# Artemis_Charger_Mod_PCB.net
KiCad netlist of a schematic drawn in EAGLE
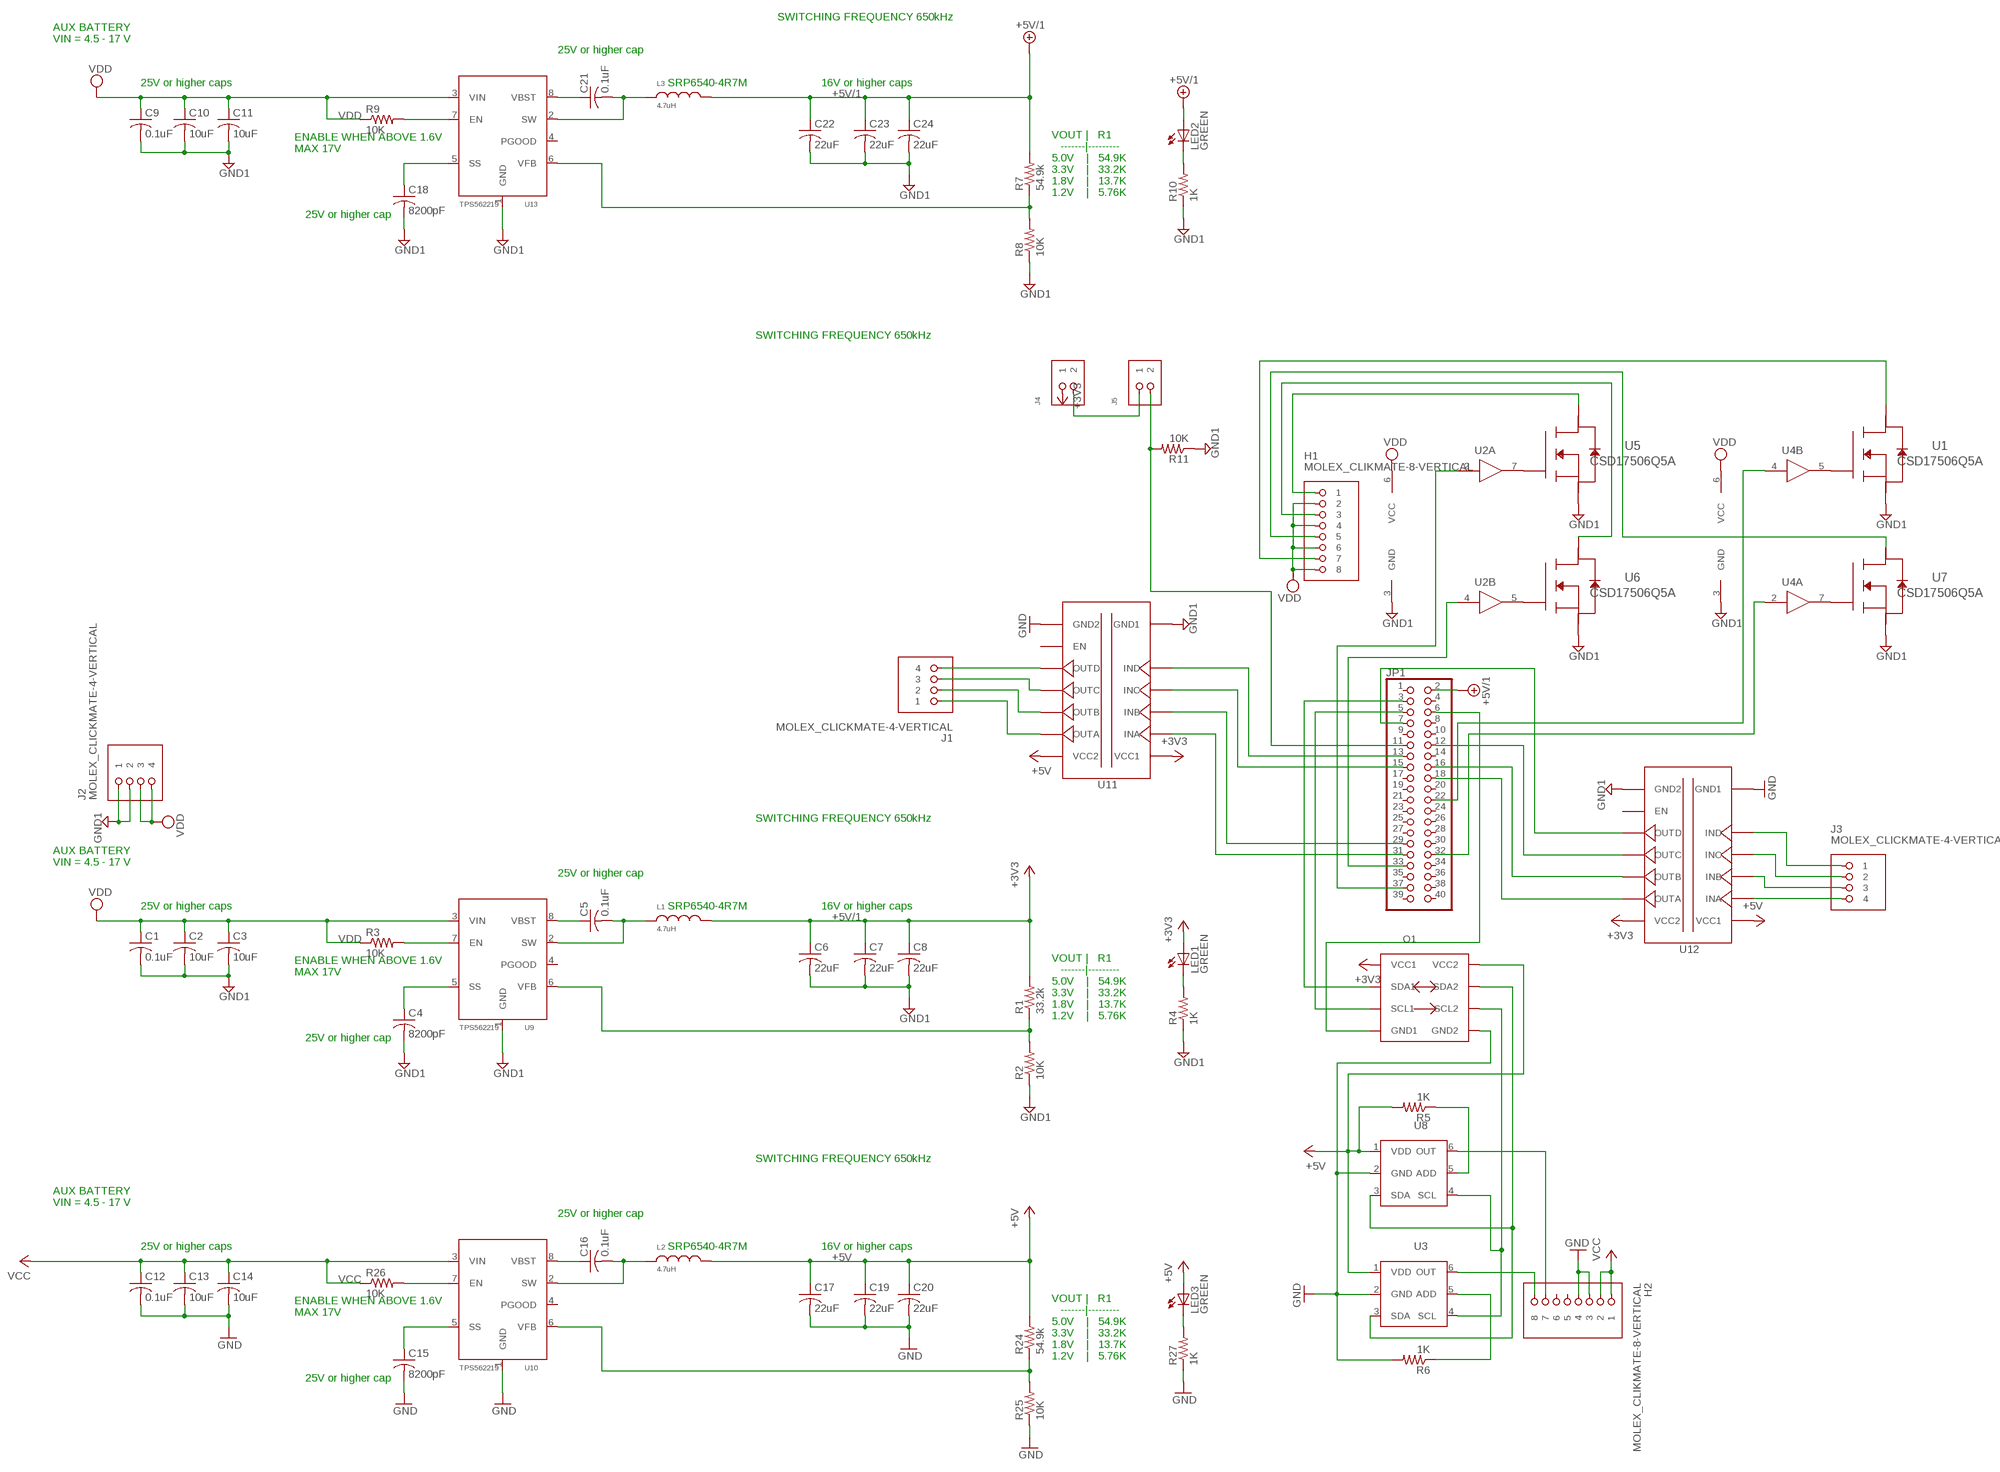
[diagram p0: schematic, sheet 1]

(export (version "E")
  (design (tool "Eeschema 10.0.6"))
  (components
    (comp (ref "C1")
      (value "0.1uF")
      (footprint "eagle-import:C0805")
      (fields (field (name "PARTNO") "GRM21BR71E104KA01L"))
      (libsource (lib "eagle-import") (part "C-USC0805"))
    )
    (comp (ref "C2")
      (value "10uF")
      (footprint "eagle-import:C0805")
      (fields (field (name "PARTNO") "GRM21BR61E106KA73L"))
      (libsource (lib "eagle-import") (part "C-USC0805"))
    )
    (comp (ref "C3")
      (value "10uF")
      (footprint "eagle-import:C0805")
      (fields (field (name "PARTNO") "GRM21BR61E106KA73L"))
      (libsource (lib "eagle-import") (part "C-USC0805"))
    )
    (comp (ref "C4")
      (value "8200pF")
      (footprint "eagle-import:C0805")
      (fields (field (name "PARTNO") "C0805C822K5RACTU"))
      (libsource (lib "eagle-import") (part "C-USC0805"))
    )
    (comp (ref "C5")
      (value "0.1uF")
      (footprint "eagle-import:C0805")
      (fields (field (name "PARTNO") "GRM21BR71E104KA01L"))
      (libsource (lib "eagle-import") (part "C-USC0805"))
    )
    (comp (ref "C6")
      (value "22uF")
      (footprint "eagle-import:C0805")
      (fields (field (name "PARTNO") "C2012JB1E226M125AC"))
      (libsource (lib "eagle-import") (part "C-USC0805"))
    )
    (comp (ref "C7")
      (value "22uF")
      (footprint "eagle-import:C0805")
      (fields (field (name "PARTNO") "C2012JB1E226M125AC"))
      (libsource (lib "eagle-import") (part "C-USC0805"))
    )
    (comp (ref "C8")
      (value "22uF")
      (footprint "eagle-import:C0805")
      (fields (field (name "PARTNO") "C2012JB1E226M125AC"))
      (libsource (lib "eagle-import") (part "C-USC0805"))
    )
    (comp (ref "C9")
      (value "0.1uF")
      (footprint "eagle-import:C0805")
      (fields (field (name "PARTNO") "GRM21BR71E104KA01L"))
      (libsource (lib "eagle-import") (part "C-USC0805"))
    )
    (comp (ref "C10")
      (value "10uF")
      (footprint "eagle-import:C0805")
      (fields (field (name "PARTNO") "GRM21BR61E106KA73L"))
      (libsource (lib "eagle-import") (part "C-USC0805"))
    )
    (comp (ref "C11")
      (value "10uF")
      (footprint "eagle-import:C0805")
      (fields (field (name "PARTNO") "GRM21BR61E106KA73L"))
      (libsource (lib "eagle-import") (part "C-USC0805"))
    )
    (comp (ref "C12")
      (value "0.1uF")
      (footprint "eagle-import:C0805")
      (fields (field (name "PARTNO") "GRM21BR71E104KA01L"))
      (libsource (lib "eagle-import") (part "C-USC0805"))
    )
    (comp (ref "C13")
      (value "10uF")
      (footprint "eagle-import:C0805")
      (fields (field (name "PARTNO") "GRM21BR61E106KA73L"))
      (libsource (lib "eagle-import") (part "C-USC0805"))
    )
    (comp (ref "C14")
      (value "10uF")
      (footprint "eagle-import:C0805")
      (fields (field (name "PARTNO") "GRM21BR61E106KA73L"))
      (libsource (lib "eagle-import") (part "C-USC0805"))
    )
    (comp (ref "C15")
      (value "8200pF")
      (footprint "eagle-import:C0805")
      (fields (field (name "PARTNO") "C0805C822K5RACTU"))
      (libsource (lib "eagle-import") (part "C-USC0805"))
    )
    (comp (ref "C16")
      (value "0.1uF")
      (footprint "eagle-import:C0805")
      (fields (field (name "PARTNO") "GRM21BR71E104KA01L"))
      (libsource (lib "eagle-import") (part "C-USC0805"))
    )
    (comp (ref "C17")
      (value "22uF")
      (footprint "eagle-import:C0805")
      (fields (field (name "PARTNO") "C2012JB1E226M125AC"))
      (libsource (lib "eagle-import") (part "C-USC0805"))
    )
    (comp (ref "C18")
      (value "8200pF")
      (footprint "eagle-import:C0805")
      (fields (field (name "PARTNO") "C0805C822K5RACTU"))
      (libsource (lib "eagle-import") (part "C-USC0805"))
    )
    (comp (ref "C19")
      (value "22uF")
      (footprint "eagle-import:C0805")
      (fields (field (name "PARTNO") "C2012JB1E226M125AC"))
      (libsource (lib "eagle-import") (part "C-USC0805"))
    )
    (comp (ref "C20")
      (value "22uF")
      (footprint "eagle-import:C0805")
      (fields (field (name "PARTNO") "C2012JB1E226M125AC"))
      (libsource (lib "eagle-import") (part "C-USC0805"))
    )
    (comp (ref "C21")
      (value "0.1uF")
      (footprint "eagle-import:C0805")
      (fields (field (name "PARTNO") "GRM21BR71E104KA01L"))
      (libsource (lib "eagle-import") (part "C-USC0805"))
    )
    (comp (ref "C22")
      (value "22uF")
      (footprint "eagle-import:C0805")
      (fields (field (name "PARTNO") "C2012JB1E226M125AC"))
      (libsource (lib "eagle-import") (part "C-USC0805"))
    )
    (comp (ref "C23")
      (value "22uF")
      (footprint "eagle-import:C0805")
      (fields (field (name "PARTNO") "C2012JB1E226M125AC"))
      (libsource (lib "eagle-import") (part "C-USC0805"))
    )
    (comp (ref "C24")
      (value "22uF")
      (footprint "eagle-import:C0805")
      (fields (field (name "PARTNO") "C2012JB1E226M125AC"))
      (libsource (lib "eagle-import") (part "C-USC0805"))
    )
    (comp (ref "H1")
      (value "MOLEX_CLIKMATE-8-VERTICAL")
      (footprint "eagle-import:MOLEX-CLIKMATE-8-VERTICAL-HEADER")
      (libsource (lib "eagle-import") (part "MOLEX_CLIKMATE-8-VERTICAL"))
    )
    (comp (ref "H2")
      (value "MOLEX_CLIKMATE-8-VERTICAL")
      (footprint "eagle-import:MOLEX-CLIKMATE-8-VERTICAL-HEADER")
      (libsource (lib "eagle-import") (part "MOLEX_CLIKMATE-8-VERTICAL"))
    )
    (comp (ref "J1")
      (value "MOLEX_CLICKMATE-4-VERTICAL")
      (footprint "eagle-import:MOLEX-CLIKMATE-4-VERTICAL-HEADER")
      (libsource (lib "eagle-import") (part "MOLEX_CLICKMATE-4-VERTICAL"))
    )
    (comp (ref "J2")
      (value "MOLEX_CLICKMATE-4-VERTICAL")
      (footprint "eagle-import:MOLEX-CLIKMATE-4-VERTICAL-HEADER")
      (libsource (lib "eagle-import") (part "MOLEX_CLICKMATE-4-VERTICAL"))
    )
    (comp (ref "J3")
      (value "MOLEX_CLICKMATE-4-VERTICAL")
      (footprint "eagle-import:MOLEX-CLIKMATE-4-VERTICAL-HEADER")
      (libsource (lib "eagle-import") (part "MOLEX_CLICKMATE-4-VERTICAL"))
    )
    (comp (ref "J4")
      (value "MOLEX_CLICKMATE-2-VERTICAL")
      (footprint "eagle-import:MOLEX-CLIKMATE-2-VERTICAL-HEADER")
      (libsource (lib "eagle-import") (part "MOLEX_CLICKMATE-2-VERTICAL"))
    )
    (comp (ref "J5")
      (value "MOLEX_CLICKMATE-2-VERTICAL")
      (footprint "eagle-import:MOLEX-CLIKMATE-2-VERTICAL-HEADER")
      (libsource (lib "eagle-import") (part "MOLEX_CLICKMATE-2-VERTICAL"))
    )
    (comp (ref "JP1")
      (value "PINHD-2X20")
      (footprint "eagle-import:2X20")
      (libsource (lib "eagle-import") (part "PINHD-2X20"))
    )
    (comp (ref "L1")
      (value "4.7uH")
      (footprint "eagle-import:SRP6540")
      (fields (field (name "PARTNO") "SRP6540-4R7M"))
      (libsource (lib "eagle-import") (part "SRP6540"))
    )
    (comp (ref "L2")
      (value "4.7uH")
      (footprint "eagle-import:SRP6540")
      (fields (field (name "PARTNO") "SRP6540-4R7M"))
      (libsource (lib "eagle-import") (part "SRP6540"))
    )
    (comp (ref "L3")
      (value "4.7uH")
      (footprint "eagle-import:SRP6540")
      (fields (field (name "PARTNO") "SRP6540-4R7M"))
      (libsource (lib "eagle-import") (part "SRP6540"))
    )
    (comp (ref "LED1")
      (value "GREEN")
      (footprint "eagle-import:CHIPLED_0805")
      (fields (field (name "PARTNO") "598-8170-107F"))
      (libsource (lib "eagle-import") (part "LEDCHIPLED_0805"))
    )
    (comp (ref "LED2")
      (value "GREEN")
      (footprint "eagle-import:CHIPLED_0805")
      (fields (field (name "PARTNO") "598-8170-107F"))
      (libsource (lib "eagle-import") (part "LEDCHIPLED_0805"))
    )
    (comp (ref "LED3")
      (value "GREEN")
      (footprint "eagle-import:CHIPLED_0805")
      (fields (field (name "PARTNO") "598-8170-107F"))
      (libsource (lib "eagle-import") (part "LEDCHIPLED_0805"))
    )
    (comp (ref "O1")
      (value "ISO1541")
      (footprint "eagle-import:ISO1541")
      (libsource (lib "eagle-import") (part "ISO1541"))
    )
    (comp (ref "R1")
      (value "33.2k")
      (footprint "eagle-import:R0805")
      (fields (field (name "PARTNO") "ERA-6AEB5492V"))
      (libsource (lib "eagle-import") (part "R-US_R0805"))
    )
    (comp (ref "R2")
      (value "10K")
      (footprint "eagle-import:R0805")
      (fields (field (name "PARTNO") "ERJ-6ENF1002V"))
      (libsource (lib "eagle-import") (part "R-US_R0805"))
    )
    (comp (ref "R3")
      (value "10K")
      (footprint "eagle-import:R0805")
      (fields (field (name "PARTNO") "ERJ-6ENF1002V"))
      (libsource (lib "eagle-import") (part "R-US_R0805"))
    )
    (comp (ref "R4")
      (value "1K")
      (footprint "eagle-import:R0805")
      (fields (field (name "PARTNO") "ERJ-6ENF1001V"))
      (libsource (lib "eagle-import") (part "R-US_R0805"))
    )
    (comp (ref "R5")
      (value "1K")
      (footprint "eagle-import:R0805")
      (fields (field (name "PARTNO") "ERJ-6ENF1001V"))
      (libsource (lib "eagle-import") (part "R-US_R0805"))
    )
    (comp (ref "R6")
      (value "1K")
      (footprint "eagle-import:R0805")
      (fields (field (name "PARTNO") "ERJ-6ENF1001V"))
      (libsource (lib "eagle-import") (part "R-US_R0805"))
    )
    (comp (ref "R7")
      (value "54.9k")
      (footprint "eagle-import:R0805")
      (fields (field (name "PARTNO") "ERA-6AEB5492V"))
      (libsource (lib "eagle-import") (part "R-US_R0805"))
    )
    (comp (ref "R8")
      (value "10K")
      (footprint "eagle-import:R0805")
      (fields (field (name "PARTNO") "ERJ-6ENF1002V"))
      (libsource (lib "eagle-import") (part "R-US_R0805"))
    )
    (comp (ref "R9")
      (value "10K")
      (footprint "eagle-import:R0805")
      (fields (field (name "PARTNO") "ERJ-6ENF1002V"))
      (libsource (lib "eagle-import") (part "R-US_R0805"))
    )
    (comp (ref "R10")
      (value "1K")
      (footprint "eagle-import:R0805")
      (fields (field (name "PARTNO") "ERJ-6ENF1001V"))
      (libsource (lib "eagle-import") (part "R-US_R0805"))
    )
    (comp (ref "R11")
      (value "10K")
      (footprint "eagle-import:R0805")
      (fields (field (name "PARTNO") "ERJ-6ENF1002V"))
      (libsource (lib "eagle-import") (part "R-US_R0805"))
    )
    (comp (ref "R24")
      (value "54.9k")
      (footprint "eagle-import:R0805")
      (fields (field (name "PARTNO") "ERA-6AEB5492V"))
      (libsource (lib "eagle-import") (part "R-US_R0805"))
    )
    (comp (ref "R25")
      (value "10K")
      (footprint "eagle-import:R0805")
      (fields (field (name "PARTNO") "ERJ-6ENF1002V"))
      (libsource (lib "eagle-import") (part "R-US_R0805"))
    )
    (comp (ref "R26")
      (value "10K")
      (footprint "eagle-import:R0805")
      (fields (field (name "PARTNO") "ERJ-6ENF1002V"))
      (libsource (lib "eagle-import") (part "R-US_R0805"))
    )
    (comp (ref "R27")
      (value "1K")
      (footprint "eagle-import:R0805")
      (fields (field (name "PARTNO") "ERJ-6ENF1001V"))
      (libsource (lib "eagle-import") (part "R-US_R0805"))
    )
    (comp (ref "U1")
      (value "CSD17506Q5A")
      (footprint "eagle-import:SON_5X6")
      (libsource (lib "eagle-import") (part "CSD17506Q5A"))
    )
    (comp (ref "U2")
      (value "FAN3214")
      (footprint "eagle-import:FAN3214")
      (libsource (lib "eagle-import") (part "FAN3214"))
    )
    (comp (ref "U3")
      (value "MAX5812")
      (footprint "eagle-import:MAX5812")
      (libsource (lib "eagle-import") (part "MAX5812M"))
    )
    (comp (ref "U4")
      (value "FAN3214")
      (footprint "eagle-import:FAN3214")
      (libsource (lib "eagle-import") (part "FAN3214"))
    )
    (comp (ref "U5")
      (value "CSD17506Q5A")
      (footprint "eagle-import:SON_5X6")
      (libsource (lib "eagle-import") (part "CSD17506Q5A"))
    )
    (comp (ref "U6")
      (value "CSD17506Q5A")
      (footprint "eagle-import:SON_5X6")
      (libsource (lib "eagle-import") (part "CSD17506Q5A"))
    )
    (comp (ref "U7")
      (value "CSD17506Q5A")
      (footprint "eagle-import:SON_5X6")
      (libsource (lib "eagle-import") (part "CSD17506Q5A"))
    )
    (comp (ref "U8")
      (value "MAX5812")
      (footprint "eagle-import:MAX5812")
      (libsource (lib "eagle-import") (part "MAX5812M"))
    )
    (comp (ref "U9")
      (value "TPS562219")
      (footprint "eagle-import:TPS562219")
      (fields (field (name "PARTNO") "TPS562219DDFT"))
      (libsource (lib "eagle-import") (part "TPS562219"))
    )
    (comp (ref "U10")
      (value "TPS562219")
      (footprint "eagle-import:TPS562219")
      (fields (field (name "PARTNO") "TPS562219DDFT"))
      (libsource (lib "eagle-import") (part "TPS562219"))
    )
    (comp (ref "U11")
      (value "ISO7340")
      (footprint "eagle-import:ISO734X")
      (libsource (lib "eagle-import") (part "ISO7340"))
    )
    (comp (ref "U12")
      (value "ISO7340")
      (footprint "eagle-import:ISO734X")
      (libsource (lib "eagle-import") (part "ISO7340"))
    )
    (comp (ref "U13")
      (value "TPS562219")
      (footprint "eagle-import:TPS562219")
      (fields (field (name "PARTNO") "TPS562219DDFT"))
      (libsource (lib "eagle-import") (part "TPS562219"))
    )
  )
  (nets
    (net (code "1") (name "+3V3") (class "Default")
      (node (ref "C22") (pin "1") (pinfunction "1_1") (pintype "passive"))
      (node (ref "C23") (pin "1") (pinfunction "1_1") (pintype "passive"))
      (node (ref "C24") (pin "1") (pinfunction "1_1") (pintype "passive"))
      (node (ref "C6") (pin "1") (pinfunction "1_1") (pintype "passive"))
      (node (ref "C7") (pin "1") (pinfunction "1_1") (pintype "passive"))
      (node (ref "C8") (pin "1") (pinfunction "1_1") (pintype "passive"))
      (node (ref "J4") (pin "1") (pinfunction "1_1") (pintype "bidirectional"))
      (node (ref "JP1") (pin "2") (pinfunction "2_2") (pintype "passive"))
      (node (ref "L1") (pin "P$2") (pinfunction "P$2_P$2") (pintype "bidirectional"))
      (node (ref "L3") (pin "P$2") (pinfunction "P$2_P$2") (pintype "bidirectional"))
      (node (ref "LED1") (pin "A") (pinfunction "A_A") (pintype "passive"))
      (node (ref "LED2") (pin "A") (pinfunction "A_A") (pintype "passive"))
      (node (ref "O1") (pin "1") (pinfunction "VCC1_1") (pintype "bidirectional"))
      (node (ref "R1") (pin "2") (pinfunction "2_2") (pintype "passive"))
      (node (ref "R7") (pin "2") (pinfunction "2_2") (pintype "passive"))
      (node (ref "U11") (pin "P$1") (pinfunction "VCC1_P$1") (pintype "bidirectional"))
      (node (ref "U12") (pin "P$16") (pinfunction "VCC2_P$16") (pintype "bidirectional"))
    )
    (net (code "2") (name "+5V") (class "Default")
      (node (ref "C17") (pin "1") (pinfunction "1_1") (pintype "passive"))
      (node (ref "C19") (pin "1") (pinfunction "1_1") (pintype "passive"))
      (node (ref "C20") (pin "1") (pinfunction "1_1") (pintype "passive"))
      (node (ref "L2") (pin "P$2") (pinfunction "P$2_P$2") (pintype "bidirectional"))
      (node (ref "LED3") (pin "A") (pinfunction "A_A") (pintype "passive"))
      (node (ref "O1") (pin "8") (pinfunction "VCC2_8") (pintype "bidirectional"))
      (node (ref "R24") (pin "2") (pinfunction "2_2") (pintype "passive"))
      (node (ref "R5") (pin "2") (pinfunction "2_2") (pintype "passive"))
      (node (ref "U11") (pin "P$16") (pinfunction "VCC2_P$16") (pintype "bidirectional"))
      (node (ref "U12") (pin "P$1") (pinfunction "VCC1_P$1") (pintype "bidirectional"))
      (node (ref "U3") (pin "1") (pinfunction "VDD_1") (pintype "bidirectional"))
      (node (ref "U8") (pin "1") (pinfunction "VDD_1") (pintype "bidirectional"))
    )
    (net (code "3") (name "GND") (class "Default")
      (node (ref "C12") (pin "2") (pinfunction "2_2") (pintype "passive"))
      (node (ref "C13") (pin "2") (pinfunction "2_2") (pintype "passive"))
      (node (ref "C14") (pin "2") (pinfunction "2_2") (pintype "passive"))
      (node (ref "C15") (pin "2") (pinfunction "2_2") (pintype "passive"))
      (node (ref "C17") (pin "2") (pinfunction "2_2") (pintype "passive"))
      (node (ref "C19") (pin "2") (pinfunction "2_2") (pintype "passive"))
      (node (ref "C20") (pin "2") (pinfunction "2_2") (pintype "passive"))
      (node (ref "H2") (pin "3") (pinfunction "3_3") (pintype "bidirectional"))
      (node (ref "H2") (pin "4") (pinfunction "4_4") (pintype "bidirectional"))
      (node (ref "O1") (pin "5") (pinfunction "GND2_5") (pintype "bidirectional"))
      (node (ref "R25") (pin "1") (pinfunction "1_1") (pintype "passive"))
      (node (ref "R27") (pin "1") (pinfunction "1_1") (pintype "passive"))
      (node (ref "R6") (pin "2") (pinfunction "2_2") (pintype "passive"))
      (node (ref "U10") (pin "1") (pinfunction "GND_1") (pintype "bidirectional"))
      (node (ref "U11") (pin "P$15") (pinfunction "GND2_P$15") (pintype "bidirectional"))
      (node (ref "U11") (pin "P$9") (pinfunction "GND2_P$9") (pintype "bidirectional"))
      (node (ref "U12") (pin "P$2") (pinfunction "GND1_P$2") (pintype "bidirectional"))
      (node (ref "U12") (pin "P$8") (pinfunction "GND1_P$8") (pintype "bidirectional"))
      (node (ref "U3") (pin "2") (pinfunction "GND_2") (pintype "bidirectional"))
      (node (ref "U8") (pin "2") (pinfunction "GND_2") (pintype "bidirectional"))
    )
    (net (code "4") (name "GND1") (class "Default")
      (node (ref "C1") (pin "2") (pinfunction "2_2") (pintype "passive"))
      (node (ref "C10") (pin "2") (pinfunction "2_2") (pintype "passive"))
      (node (ref "C11") (pin "2") (pinfunction "2_2") (pintype "passive"))
      (node (ref "C18") (pin "2") (pinfunction "2_2") (pintype "passive"))
      (node (ref "C2") (pin "2") (pinfunction "2_2") (pintype "passive"))
      (node (ref "C22") (pin "2") (pinfunction "2_2") (pintype "passive"))
      (node (ref "C23") (pin "2") (pinfunction "2_2") (pintype "passive"))
      (node (ref "C24") (pin "2") (pinfunction "2_2") (pintype "passive"))
      (node (ref "C3") (pin "2") (pinfunction "2_2") (pintype "passive"))
      (node (ref "C4") (pin "2") (pinfunction "2_2") (pintype "passive"))
      (node (ref "C6") (pin "2") (pinfunction "2_2") (pintype "passive"))
      (node (ref "C7") (pin "2") (pinfunction "2_2") (pintype "passive"))
      (node (ref "C8") (pin "2") (pinfunction "2_2") (pintype "passive"))
      (node (ref "C9") (pin "2") (pinfunction "2_2") (pintype "passive"))
      (node (ref "J2") (pin "1") (pinfunction "1_1") (pintype "bidirectional"))
      (node (ref "J2") (pin "2") (pinfunction "2_2") (pintype "bidirectional"))
      (node (ref "R10") (pin "1") (pinfunction "1_1") (pintype "passive"))
      (node (ref "R11") (pin "1") (pinfunction "1_1") (pintype "passive"))
      (node (ref "R2") (pin "1") (pinfunction "1_1") (pintype "passive"))
      (node (ref "R4") (pin "1") (pinfunction "1_1") (pintype "passive"))
      (node (ref "R8") (pin "1") (pinfunction "1_1") (pintype "passive"))
      (node (ref "U1") (pin "1") (pinfunction "S_1") (pintype "bidirectional"))
      (node (ref "U1") (pin "2") (pinfunction "S_2") (pintype "bidirectional"))
      (node (ref "U1") (pin "3") (pinfunction "S_3") (pintype "bidirectional"))
      (node (ref "U11") (pin "P$2") (pinfunction "GND1_P$2") (pintype "bidirectional"))
      (node (ref "U11") (pin "P$8") (pinfunction "GND1_P$8") (pintype "bidirectional"))
      (node (ref "U12") (pin "P$15") (pinfunction "GND2_P$15") (pintype "bidirectional"))
      (node (ref "U12") (pin "P$9") (pinfunction "GND2_P$9") (pintype "bidirectional"))
      (node (ref "U13") (pin "1") (pinfunction "GND_1") (pintype "bidirectional"))
      (node (ref "U2") (pin "3") (pinfunction "GND_3") (pintype "power_in"))
      (node (ref "U4") (pin "3") (pinfunction "GND_3") (pintype "power_in"))
      (node (ref "U5") (pin "1") (pinfunction "S_1") (pintype "bidirectional"))
      (node (ref "U5") (pin "2") (pinfunction "S_2") (pintype "bidirectional"))
      (node (ref "U5") (pin "3") (pinfunction "S_3") (pintype "bidirectional"))
      (node (ref "U6") (pin "1") (pinfunction "S_1") (pintype "bidirectional"))
      (node (ref "U6") (pin "2") (pinfunction "S_2") (pintype "bidirectional"))
      (node (ref "U6") (pin "3") (pinfunction "S_3") (pintype "bidirectional"))
      (node (ref "U7") (pin "1") (pinfunction "S_1") (pintype "bidirectional"))
      (node (ref "U7") (pin "2") (pinfunction "S_2") (pintype "bidirectional"))
      (node (ref "U7") (pin "3") (pinfunction "S_3") (pintype "bidirectional"))
      (node (ref "U9") (pin "1") (pinfunction "GND_1") (pintype "bidirectional"))
    )
    (net (code "5") (name "Net-(H1-Pad1)") (class "Default")
      (node (ref "H1") (pin "1") (pinfunction "1_1") (pintype "bidirectional"))
      (node (ref "U5") (pin "5") (pinfunction "D_5") (pintype "bidirectional"))
      (node (ref "U5") (pin "6") (pinfunction "D_6") (pintype "bidirectional"))
      (node (ref "U5") (pin "7") (pinfunction "D_7") (pintype "bidirectional"))
      (node (ref "U5") (pin "8") (pinfunction "D_8") (pintype "bidirectional"))
      (node (ref "U5") (pin "PAD") (pinfunction "D_PAD") (pintype "bidirectional"))
      (node (ref "U5") (pin "PAD1") (pinfunction "D_PAD1") (pintype "bidirectional"))
      (node (ref "U5") (pin "VIA1") (pinfunction "D_VIA1") (pintype "bidirectional"))
      (node (ref "U5") (pin "VIA2") (pinfunction "D_VIA2") (pintype "bidirectional"))
      (node (ref "U5") (pin "VIA3") (pinfunction "D_VIA3") (pintype "bidirectional"))
      (node (ref "U5") (pin "VIA4") (pinfunction "D_VIA4") (pintype "bidirectional"))
      (node (ref "U5") (pin "VIA5") (pinfunction "D_VIA5") (pintype "bidirectional"))
      (node (ref "U5") (pin "VIA6") (pinfunction "D_VIA6") (pintype "bidirectional"))
      (node (ref "U5") (pin "VIA7") (pinfunction "D_VIA7") (pintype "bidirectional"))
      (node (ref "U5") (pin "VIA8") (pinfunction "D_VIA8") (pintype "bidirectional"))
      (node (ref "U5") (pin "VIA9") (pinfunction "D_VIA9") (pintype "bidirectional"))
    )
    (net (code "6") (name "Net-(H1-Pad3)") (class "Default")
      (node (ref "H1") (pin "3") (pinfunction "3_3") (pintype "bidirectional"))
      (node (ref "U6") (pin "5") (pinfunction "D_5") (pintype "bidirectional"))
      (node (ref "U6") (pin "6") (pinfunction "D_6") (pintype "bidirectional"))
      (node (ref "U6") (pin "7") (pinfunction "D_7") (pintype "bidirectional"))
      (node (ref "U6") (pin "8") (pinfunction "D_8") (pintype "bidirectional"))
      (node (ref "U6") (pin "PAD") (pinfunction "D_PAD") (pintype "bidirectional"))
      (node (ref "U6") (pin "PAD1") (pinfunction "D_PAD1") (pintype "bidirectional"))
      (node (ref "U6") (pin "VIA1") (pinfunction "D_VIA1") (pintype "bidirectional"))
      (node (ref "U6") (pin "VIA2") (pinfunction "D_VIA2") (pintype "bidirectional"))
      (node (ref "U6") (pin "VIA3") (pinfunction "D_VIA3") (pintype "bidirectional"))
      (node (ref "U6") (pin "VIA4") (pinfunction "D_VIA4") (pintype "bidirectional"))
      (node (ref "U6") (pin "VIA5") (pinfunction "D_VIA5") (pintype "bidirectional"))
      (node (ref "U6") (pin "VIA6") (pinfunction "D_VIA6") (pintype "bidirectional"))
      (node (ref "U6") (pin "VIA7") (pinfunction "D_VIA7") (pintype "bidirectional"))
      (node (ref "U6") (pin "VIA8") (pinfunction "D_VIA8") (pintype "bidirectional"))
      (node (ref "U6") (pin "VIA9") (pinfunction "D_VIA9") (pintype "bidirectional"))
    )
    (net (code "7") (name "Net-(H1-Pad5)") (class "Default")
      (node (ref "H1") (pin "5") (pinfunction "5_5") (pintype "bidirectional"))
      (node (ref "U7") (pin "5") (pinfunction "D_5") (pintype "bidirectional"))
      (node (ref "U7") (pin "6") (pinfunction "D_6") (pintype "bidirectional"))
      (node (ref "U7") (pin "7") (pinfunction "D_7") (pintype "bidirectional"))
      (node (ref "U7") (pin "8") (pinfunction "D_8") (pintype "bidirectional"))
      (node (ref "U7") (pin "PAD") (pinfunction "D_PAD") (pintype "bidirectional"))
      (node (ref "U7") (pin "PAD1") (pinfunction "D_PAD1") (pintype "bidirectional"))
      (node (ref "U7") (pin "VIA1") (pinfunction "D_VIA1") (pintype "bidirectional"))
      (node (ref "U7") (pin "VIA2") (pinfunction "D_VIA2") (pintype "bidirectional"))
      (node (ref "U7") (pin "VIA3") (pinfunction "D_VIA3") (pintype "bidirectional"))
      (node (ref "U7") (pin "VIA4") (pinfunction "D_VIA4") (pintype "bidirectional"))
      (node (ref "U7") (pin "VIA5") (pinfunction "D_VIA5") (pintype "bidirectional"))
      (node (ref "U7") (pin "VIA6") (pinfunction "D_VIA6") (pintype "bidirectional"))
      (node (ref "U7") (pin "VIA7") (pinfunction "D_VIA7") (pintype "bidirectional"))
      (node (ref "U7") (pin "VIA8") (pinfunction "D_VIA8") (pintype "bidirectional"))
      (node (ref "U7") (pin "VIA9") (pinfunction "D_VIA9") (pintype "bidirectional"))
    )
    (net (code "8") (name "Net-(H1-Pad7)") (class "Default")
      (node (ref "H1") (pin "7") (pinfunction "7_7") (pintype "bidirectional"))
      (node (ref "U1") (pin "5") (pinfunction "D_5") (pintype "bidirectional"))
      (node (ref "U1") (pin "6") (pinfunction "D_6") (pintype "bidirectional"))
      (node (ref "U1") (pin "7") (pinfunction "D_7") (pintype "bidirectional"))
      (node (ref "U1") (pin "8") (pinfunction "D_8") (pintype "bidirectional"))
      (node (ref "U1") (pin "PAD") (pinfunction "D_PAD") (pintype "bidirectional"))
      (node (ref "U1") (pin "PAD1") (pinfunction "D_PAD1") (pintype "bidirectional"))
      (node (ref "U1") (pin "VIA1") (pinfunction "D_VIA1") (pintype "bidirectional"))
      (node (ref "U1") (pin "VIA2") (pinfunction "D_VIA2") (pintype "bidirectional"))
      (node (ref "U1") (pin "VIA3") (pinfunction "D_VIA3") (pintype "bidirectional"))
      (node (ref "U1") (pin "VIA4") (pinfunction "D_VIA4") (pintype "bidirectional"))
      (node (ref "U1") (pin "VIA5") (pinfunction "D_VIA5") (pintype "bidirectional"))
      (node (ref "U1") (pin "VIA6") (pinfunction "D_VIA6") (pintype "bidirectional"))
      (node (ref "U1") (pin "VIA7") (pinfunction "D_VIA7") (pintype "bidirectional"))
      (node (ref "U1") (pin "VIA8") (pinfunction "D_VIA8") (pintype "bidirectional"))
      (node (ref "U1") (pin "VIA9") (pinfunction "D_VIA9") (pintype "bidirectional"))
    )
    (net (code "9") (name "Net-(J4-Pad2)") (class "Default")
      (node (ref "J4") (pin "2") (pinfunction "2_2") (pintype "bidirectional"))
      (node (ref "J5") (pin "1") (pinfunction "1_1") (pintype "bidirectional"))
    )
    (net (code "10") (name "Net-(J5-Pad2)") (class "Default")
      (node (ref "J5") (pin "2") (pinfunction "2_2") (pintype "bidirectional"))
      (node (ref "JP1") (pin "11") (pinfunction "11_11") (pintype "passive"))
      (node (ref "R11") (pin "2") (pinfunction "2_2") (pintype "passive"))
    )
    (net (code "11") (name "Net-(LED1-PadC)") (class "Default")
      (node (ref "LED1") (pin "C") (pinfunction "C_C") (pintype "passive"))
      (node (ref "R4") (pin "2") (pinfunction "2_2") (pintype "passive"))
    )
    (net (code "12") (name "Net-(LED2-PadC)") (class "Default")
      (node (ref "LED2") (pin "C") (pinfunction "C_C") (pintype "passive"))
      (node (ref "R10") (pin "2") (pinfunction "2_2") (pintype "passive"))
    )
    (net (code "13") (name "Net-(LED3-PadC)") (class "Default")
      (node (ref "LED3") (pin "C") (pinfunction "C_C") (pintype "passive"))
      (node (ref "R27") (pin "2") (pinfunction "2_2") (pintype "passive"))
    )
    (net (code "14") (name "Net-(O1-GND1)") (class "Default")
      (node (ref "JP1") (pin "6") (pinfunction "6_6") (pintype "passive"))
      (node (ref "O1") (pin "4") (pinfunction "GND1_4") (pintype "bidirectional"))
    )
    (net (code "15") (name "Net-(O1-SCL1)") (class "Default")
      (node (ref "JP1") (pin "5") (pinfunction "5_5") (pintype "passive"))
      (node (ref "O1") (pin "3") (pinfunction "SCL1_3") (pintype "bidirectional"))
    )
    (net (code "16") (name "Net-(O1-SCL2)") (class "Default")
      (node (ref "O1") (pin "6") (pinfunction "SCL2_6") (pintype "bidirectional"))
      (node (ref "U3") (pin "4") (pinfunction "SCL_4") (pintype "bidirectional"))
      (node (ref "U8") (pin "4") (pinfunction "SCL_4") (pintype "bidirectional"))
    )
    (net (code "17") (name "Net-(O1-SDA1)") (class "Default")
      (node (ref "JP1") (pin "3") (pinfunction "3_3") (pintype "passive"))
      (node (ref "O1") (pin "2") (pinfunction "SDA1_2") (pintype "bidirectional"))
    )
    (net (code "18") (name "Net-(O1-SDA2)") (class "Default")
      (node (ref "O1") (pin "7") (pinfunction "SDA2_7") (pintype "bidirectional"))
      (node (ref "U3") (pin "3") (pinfunction "SDA_3") (pintype "bidirectional"))
      (node (ref "U8") (pin "3") (pinfunction "SDA_3") (pintype "bidirectional"))
    )
    (net (code "19") (name "Net-(U1-G)") (class "Default")
      (node (ref "U1") (pin "4") (pinfunction "G_4") (pintype "input"))
      (node (ref "U4") (pin "5") (pinfunction "OUT_5") (pintype "output"))
    )
    (net (code "20") (name "Net-(U2A-IN)") (class "Default")
      (node (ref "JP1") (pin "37") (pinfunction "37_37") (pintype "passive"))
      (node (ref "U2") (pin "2") (pinfunction "IN_2") (pintype "input"))
    )
    (net (code "21") (name "Net-(U2A-OUT)") (class "Default")
      (node (ref "U2") (pin "7") (pinfunction "OUT_7") (pintype "output"))
      (node (ref "U5") (pin "4") (pinfunction "G_4") (pintype "input"))
    )
    (net (code "22") (name "Net-(U2B-IN)") (class "Default")
      (node (ref "JP1") (pin "33") (pinfunction "33_33") (pintype "passive"))
      (node (ref "U2") (pin "4") (pinfunction "IN_4") (pintype "input"))
    )
    (net (code "23") (name "Net-(U2B-OUT)") (class "Default")
      (node (ref "U2") (pin "5") (pinfunction "OUT_5") (pintype "output"))
      (node (ref "U6") (pin "4") (pinfunction "G_4") (pintype "input"))
    )
    (net (code "24") (name "Net-(U3-ADD)") (class "Default")
      (node (ref "R6") (pin "1") (pinfunction "1_1") (pintype "passive"))
      (node (ref "U3") (pin "5") (pinfunction "ADD_5") (pintype "bidirectional"))
    )
    (net (code "25") (name "Net-(U3-OUT)") (class "Default")
      (node (ref "H2") (pin "8") (pinfunction "8_8") (pintype "bidirectional"))
      (node (ref "U3") (pin "6") (pinfunction "OUT_6") (pintype "bidirectional"))
    )
    (net (code "26") (name "Net-(U4A-IN)") (class "Default")
      (node (ref "JP1") (pin "32") (pinfunction "32_32") (pintype "passive"))
      (node (ref "U4") (pin "2") (pinfunction "IN_2") (pintype "input"))
    )
    (net (code "27") (name "Net-(U4A-OUT)") (class "Default")
      (node (ref "U4") (pin "7") (pinfunction "OUT_7") (pintype "output"))
      (node (ref "U7") (pin "4") (pinfunction "G_4") (pintype "input"))
    )
    (net (code "28") (name "Net-(U4B-IN)") (class "Default")
      (node (ref "JP1") (pin "22") (pinfunction "22_22") (pintype "passive"))
      (node (ref "U4") (pin "4") (pinfunction "IN_4") (pintype "input"))
    )
    (net (code "29") (name "Net-(U8-ADD)") (class "Default")
      (node (ref "R5") (pin "1") (pinfunction "1_1") (pintype "passive"))
      (node (ref "U8") (pin "5") (pinfunction "ADD_5") (pintype "bidirectional"))
    )
    (net (code "30") (name "Net-(U8-OUT)") (class "Default")
      (node (ref "H2") (pin "7") (pinfunction "7_7") (pintype "bidirectional"))
      (node (ref "U8") (pin "6") (pinfunction "OUT_6") (pintype "bidirectional"))
    )
    (net (code "31") (name "Net-(U9-EN)") (class "Default")
      (node (ref "R3") (pin "2") (pinfunction "2_2") (pintype "passive"))
      (node (ref "U9") (pin "7") (pinfunction "EN_7") (pintype "bidirectional"))
    )
    (net (code "32") (name "Net-(U9-SS)") (class "Default")
      (node (ref "C4") (pin "1") (pinfunction "1_1") (pintype "passive"))
      (node (ref "U9") (pin "5") (pinfunction "SS_5") (pintype "bidirectional"))
    )
    (net (code "33") (name "Net-(U9-SW)") (class "Default")
      (node (ref "C5") (pin "2") (pinfunction "2_2") (pintype "passive"))
      (node (ref "L1") (pin "P$1") (pinfunction "P$1_P$1") (pintype "bidirectional"))
      (node (ref "U9") (pin "2") (pinfunction "SW_2") (pintype "bidirectional"))
    )
    (net (code "34") (name "Net-(U9-VBST)") (class "Default")
      (node (ref "C5") (pin "1") (pinfunction "1_1") (pintype "passive"))
      (node (ref "U9") (pin "8") (pinfunction "VBST_8") (pintype "bidirectional"))
    )
    (net (code "35") (name "Net-(U9-VFB)") (class "Default")
      (node (ref "R1") (pin "1") (pinfunction "1_1") (pintype "passive"))
      (node (ref "R2") (pin "2") (pinfunction "2_2") (pintype "passive"))
      (node (ref "U9") (pin "6") (pinfunction "VFB_6") (pintype "bidirectional"))
    )
    (net (code "36") (name "Net-(U10-EN)") (class "Default")
      (node (ref "R26") (pin "2") (pinfunction "2_2") (pintype "passive"))
      (node (ref "U10") (pin "7") (pinfunction "EN_7") (pintype "bidirectional"))
    )
    (net (code "37") (name "Net-(U10-SS)") (class "Default")
      (node (ref "C15") (pin "1") (pinfunction "1_1") (pintype "passive"))
      (node (ref "U10") (pin "5") (pinfunction "SS_5") (pintype "bidirectional"))
    )
    (net (code "38") (name "Net-(U10-SW)") (class "Default")
      (node (ref "C16") (pin "2") (pinfunction "2_2") (pintype "passive"))
      (node (ref "L2") (pin "P$1") (pinfunction "P$1_P$1") (pintype "bidirectional"))
      (node (ref "U10") (pin "2") (pinfunction "SW_2") (pintype "bidirectional"))
    )
    (net (code "39") (name "Net-(U10-VBST)") (class "Default")
      (node (ref "C16") (pin "1") (pinfunction "1_1") (pintype "passive"))
      (node (ref "U10") (pin "8") (pinfunction "VBST_8") (pintype "bidirectional"))
    )
    (net (code "40") (name "Net-(U10-VFB)") (class "Default")
      (node (ref "R24") (pin "1") (pinfunction "1_1") (pintype "passive"))
      (node (ref "R25") (pin "2") (pinfunction "2_2") (pintype "passive"))
      (node (ref "U10") (pin "6") (pinfunction "VFB_6") (pintype "bidirectional"))
    )
    (net (code "41") (name "Net-(U11-INA)") (class "Default")
      (node (ref "JP1") (pin "31") (pinfunction "31_31") (pintype "passive"))
      (node (ref "U11") (pin "P$3") (pinfunction "INA_P$3") (pintype "bidirectional"))
    )
    (net (code "42") (name "Net-(U11-INB)") (class "Default")
      (node (ref "JP1") (pin "29") (pinfunction "29_29") (pintype "passive"))
      (node (ref "U11") (pin "P$4") (pinfunction "INB_P$4") (pintype "bidirectional"))
    )
    (net (code "43") (name "Net-(U11-INC)") (class "Default")
      (node (ref "JP1") (pin "15") (pinfunction "15_15") (pintype "passive"))
      (node (ref "U11") (pin "P$5") (pinfunction "INC_P$5") (pintype "bidirectional"))
    )
    (net (code "44") (name "Net-(U11-IND)") (class "Default")
      (node (ref "JP1") (pin "13") (pinfunction "13_13") (pintype "passive"))
      (node (ref "U11") (pin "P$6") (pinfunction "IND_P$6") (pintype "bidirectional"))
    )
    (net (code "45") (name "Net-(U11-OUTA)") (class "Default")
      (node (ref "J1") (pin "1") (pinfunction "1_1") (pintype "bidirectional"))
      (node (ref "U11") (pin "P$14") (pinfunction "OUTA_P$14") (pintype "bidirectional"))
    )
    (net (code "46") (name "Net-(U11-OUTB)") (class "Default")
      (node (ref "J1") (pin "2") (pinfunction "2_2") (pintype "bidirectional"))
      (node (ref "U11") (pin "P$13") (pinfunction "OUTB_P$13") (pintype "bidirectional"))
    )
    (net (code "47") (name "Net-(U11-OUTC)") (class "Default")
      (node (ref "J1") (pin "3") (pinfunction "3_3") (pintype "bidirectional"))
      (node (ref "U11") (pin "P$12") (pinfunction "OUTC_P$12") (pintype "bidirectional"))
    )
    (net (code "48") (name "Net-(U11-OUTD)") (class "Default")
      (node (ref "J1") (pin "4") (pinfunction "4_4") (pintype "bidirectional"))
      (node (ref "U11") (pin "P$11") (pinfunction "OUTD_P$11") (pintype "bidirectional"))
    )
    (net (code "49") (name "Net-(U12-INA)") (class "Default")
      (node (ref "J3") (pin "4") (pinfunction "4_4") (pintype "bidirectional"))
      (node (ref "U12") (pin "P$3") (pinfunction "INA_P$3") (pintype "bidirectional"))
    )
    (net (code "50") (name "Net-(U12-INB)") (class "Default")
      (node (ref "J3") (pin "3") (pinfunction "3_3") (pintype "bidirectional"))
      (node (ref "U12") (pin "P$4") (pinfunction "INB_P$4") (pintype "bidirectional"))
    )
    (net (code "51") (name "Net-(U12-INC)") (class "Default")
      (node (ref "J3") (pin "2") (pinfunction "2_2") (pintype "bidirectional"))
      (node (ref "U12") (pin "P$5") (pinfunction "INC_P$5") (pintype "bidirectional"))
    )
    (net (code "52") (name "Net-(U12-IND)") (class "Default")
      (node (ref "J3") (pin "1") (pinfunction "1_1") (pintype "bidirectional"))
      (node (ref "U12") (pin "P$6") (pinfunction "IND_P$6") (pintype "bidirectional"))
    )
    (net (code "53") (name "Net-(U12-OUTA)") (class "Default")
      (node (ref "JP1") (pin "18") (pinfunction "18_18") (pintype "passive"))
      (node (ref "U12") (pin "P$14") (pinfunction "OUTA_P$14") (pintype "bidirectional"))
    )
    (net (code "54") (name "Net-(U12-OUTB)") (class "Default")
      (node (ref "JP1") (pin "16") (pinfunction "16_16") (pintype "passive"))
      (node (ref "U12") (pin "P$13") (pinfunction "OUTB_P$13") (pintype "bidirectional"))
    )
    (net (code "55") (name "Net-(U12-OUTC)") (class "Default")
      (node (ref "JP1") (pin "12") (pinfunction "12_12") (pintype "passive"))
      (node (ref "U12") (pin "P$12") (pinfunction "OUTC_P$12") (pintype "bidirectional"))
    )
    (net (code "56") (name "Net-(U12-OUTD)") (class "Default")
      (node (ref "JP1") (pin "7") (pinfunction "7_7") (pintype "passive"))
      (node (ref "U12") (pin "P$11") (pinfunction "OUTD_P$11") (pintype "bidirectional"))
    )
    (net (code "57") (name "Net-(U13-EN)") (class "Default")
      (node (ref "R9") (pin "2") (pinfunction "2_2") (pintype "passive"))
      (node (ref "U13") (pin "7") (pinfunction "EN_7") (pintype "bidirectional"))
    )
    (net (code "58") (name "Net-(U13-SS)") (class "Default")
      (node (ref "C18") (pin "1") (pinfunction "1_1") (pintype "passive"))
      (node (ref "U13") (pin "5") (pinfunction "SS_5") (pintype "bidirectional"))
    )
    (net (code "59") (name "Net-(U13-SW)") (class "Default")
      (node (ref "C21") (pin "2") (pinfunction "2_2") (pintype "passive"))
      (node (ref "L3") (pin "P$1") (pinfunction "P$1_P$1") (pintype "bidirectional"))
      (node (ref "U13") (pin "2") (pinfunction "SW_2") (pintype "bidirectional"))
    )
    (net (code "60") (name "Net-(U13-VBST)") (class "Default")
      (node (ref "C21") (pin "1") (pinfunction "1_1") (pintype "passive"))
      (node (ref "U13") (pin "8") (pinfunction "VBST_8") (pintype "bidirectional"))
    )
    (net (code "61") (name "Net-(U13-VFB)") (class "Default")
      (node (ref "R7") (pin "1") (pinfunction "1_1") (pintype "passive"))
      (node (ref "R8") (pin "2") (pinfunction "2_2") (pintype "passive"))
      (node (ref "U13") (pin "6") (pinfunction "VFB_6") (pintype "bidirectional"))
    )
    (net (code "62") (name "VCC") (class "Default")
      (node (ref "C12") (pin "1") (pinfunction "1_1") (pintype "passive"))
      (node (ref "C13") (pin "1") (pinfunction "1_1") (pintype "passive"))
      (node (ref "C14") (pin "1") (pinfunction "1_1") (pintype "passive"))
      (node (ref "H2") (pin "1") (pinfunction "1_1") (pintype "bidirectional"))
      (node (ref "H2") (pin "2") (pinfunction "2_2") (pintype "bidirectional"))
      (node (ref "R26") (pin "1") (pinfunction "1_1") (pintype "passive"))
      (node (ref "U10") (pin "3") (pinfunction "VIN_3") (pintype "bidirectional"))
    )
    (net (code "63") (name "VDD") (class "Default")
      (node (ref "C1") (pin "1") (pinfunction "1_1") (pintype "passive"))
      (node (ref "C10") (pin "1") (pinfunction "1_1") (pintype "passive"))
      (node (ref "C11") (pin "1") (pinfunction "1_1") (pintype "passive"))
      (node (ref "C2") (pin "1") (pinfunction "1_1") (pintype "passive"))
      (node (ref "C3") (pin "1") (pinfunction "1_1") (pintype "passive"))
      (node (ref "C9") (pin "1") (pinfunction "1_1") (pintype "passive"))
      (node (ref "H1") (pin "2") (pinfunction "2_2") (pintype "bidirectional"))
      (node (ref "H1") (pin "4") (pinfunction "4_4") (pintype "bidirectional"))
      (node (ref "H1") (pin "6") (pinfunction "6_6") (pintype "bidirectional"))
      (node (ref "H1") (pin "8") (pinfunction "8_8") (pintype "bidirectional"))
      (node (ref "J2") (pin "3") (pinfunction "3_3") (pintype "bidirectional"))
      (node (ref "J2") (pin "4") (pinfunction "4_4") (pintype "bidirectional"))
      (node (ref "R3") (pin "1") (pinfunction "1_1") (pintype "passive"))
      (node (ref "R9") (pin "1") (pinfunction "1_1") (pintype "passive"))
      (node (ref "U13") (pin "3") (pinfunction "VIN_3") (pintype "bidirectional"))
      (node (ref "U2") (pin "6") (pinfunction "VCC_6") (pintype "power_in"))
      (node (ref "U4") (pin "6") (pinfunction "VCC_6") (pintype "power_in"))
      (node (ref "U9") (pin "3") (pinfunction "VIN_3") (pintype "bidirectional"))
    )
    (net (code "64") (name "unconnected-(H2-Pad5)") (class "Default")
      (node (ref "H2") (pin "5") (pinfunction "5_5") (pintype "bidirectional"))
    )
    (net (code "65") (name "unconnected-(H2-Pad6)") (class "Default")
      (node (ref "H2") (pin "6") (pinfunction "6_6") (pintype "bidirectional"))
    )
    (net (code "66") (name "unconnected-(JP1-Pad1)") (class "Default")
      (node (ref "JP1") (pin "1") (pinfunction "1_1") (pintype "passive"))
    )
    (net (code "67") (name "unconnected-(JP1-Pad4)") (class "Default")
      (node (ref "JP1") (pin "4") (pinfunction "4_4") (pintype "passive"))
    )
    (net (code "68") (name "unconnected-(JP1-Pad8)") (class "Default")
      (node (ref "JP1") (pin "8") (pinfunction "8_8") (pintype "passive"))
    )
    (net (code "69") (name "unconnected-(JP1-Pad9)") (class "Default")
      (node (ref "JP1") (pin "9") (pinfunction "9_9") (pintype "passive"))
    )
    (net (code "70") (name "unconnected-(JP1-Pad10)") (class "Default")
      (node (ref "JP1") (pin "10") (pinfunction "10_10") (pintype "passive"))
    )
    (net (code "71") (name "unconnected-(JP1-Pad14)") (class "Default")
      (node (ref "JP1") (pin "14") (pinfunction "14_14") (pintype "passive"))
    )
    (net (code "72") (name "unconnected-(JP1-Pad17)") (class "Default")
      (node (ref "JP1") (pin "17") (pinfunction "17_17") (pintype "passive"))
    )
    (net (code "73") (name "unconnected-(JP1-Pad19)") (class "Default")
      (node (ref "JP1") (pin "19") (pinfunction "19_19") (pintype "passive"))
    )
    (net (code "74") (name "unconnected-(JP1-Pad20)") (class "Default")
      (node (ref "JP1") (pin "20") (pinfunction "20_20") (pintype "passive"))
    )
    (net (code "75") (name "unconnected-(JP1-Pad21)") (class "Default")
      (node (ref "JP1") (pin "21") (pinfunction "21_21") (pintype "passive"))
    )
    (net (code "76") (name "unconnected-(JP1-Pad23)") (class "Default")
      (node (ref "JP1") (pin "23") (pinfunction "23_23") (pintype "passive"))
    )
    (net (code "77") (name "unconnected-(JP1-Pad24)") (class "Default")
      (node (ref "JP1") (pin "24") (pinfunction "24_24") (pintype "passive"))
    )
    (net (code "78") (name "unconnected-(JP1-Pad25)") (class "Default")
      (node (ref "JP1") (pin "25") (pinfunction "25_25") (pintype "passive"))
    )
    (net (code "79") (name "unconnected-(JP1-Pad26)") (class "Default")
      (node (ref "JP1") (pin "26") (pinfunction "26_26") (pintype "passive"))
    )
    (net (code "80") (name "unconnected-(JP1-Pad27)") (class "Default")
      (node (ref "JP1") (pin "27") (pinfunction "27_27") (pintype "passive"))
    )
    (net (code "81") (name "unconnected-(JP1-Pad28)") (class "Default")
      (node (ref "JP1") (pin "28") (pinfunction "28_28") (pintype "passive"))
    )
    (net (code "82") (name "unconnected-(JP1-Pad30)") (class "Default")
      (node (ref "JP1") (pin "30") (pinfunction "30_30") (pintype "passive"))
    )
    (net (code "83") (name "unconnected-(JP1-Pad34)") (class "Default")
      (node (ref "JP1") (pin "34") (pinfunction "34_34") (pintype "passive"))
    )
    (net (code "84") (name "unconnected-(JP1-Pad35)") (class "Default")
      (node (ref "JP1") (pin "35") (pinfunction "35_35") (pintype "passive"))
    )
    (net (code "85") (name "unconnected-(JP1-Pad36)") (class "Default")
      (node (ref "JP1") (pin "36") (pinfunction "36_36") (pintype "passive"))
    )
    (net (code "86") (name "unconnected-(JP1-Pad38)") (class "Default")
      (node (ref "JP1") (pin "38") (pinfunction "38_38") (pintype "passive"))
    )
    (net (code "87") (name "unconnected-(JP1-Pad39)") (class "Default")
      (node (ref "JP1") (pin "39") (pinfunction "39_39") (pintype "passive"))
    )
    (net (code "88") (name "unconnected-(JP1-Pad40)") (class "Default")
      (node (ref "JP1") (pin "40") (pinfunction "40_40") (pintype "passive"))
    )
    (net (code "89") (name "unconnected-(U9-PGOOD-Pad4)") (class "Default")
      (node (ref "U9") (pin "4") (pinfunction "PGOOD_4") (pintype "bidirectional"))
    )
    (net (code "90") (name "unconnected-(U10-PGOOD-Pad4)") (class "Default")
      (node (ref "U10") (pin "4") (pinfunction "PGOOD_4") (pintype "bidirectional"))
    )
    (net (code "91") (name "unconnected-(U11-EN-PadP$10)") (class "Default")
      (node (ref "U11") (pin "P$10") (pinfunction "EN_P$10") (pintype "bidirectional"))
    )
    (net (code "92") (name "unconnected-(U12-EN-PadP$10)") (class "Default")
      (node (ref "U12") (pin "P$10") (pinfunction "EN_P$10") (pintype "bidirectional"))
    )
    (net (code "93") (name "unconnected-(U13-PGOOD-Pad4)") (class "Default")
      (node (ref "U13") (pin "4") (pinfunction "PGOOD_4") (pintype "bidirectional"))
    )
  )
)
